# SCH_MSX_nano_mouse_v0_4_2024-05-15.net
KiCad netlist of a schematic drawn in EasyEDA
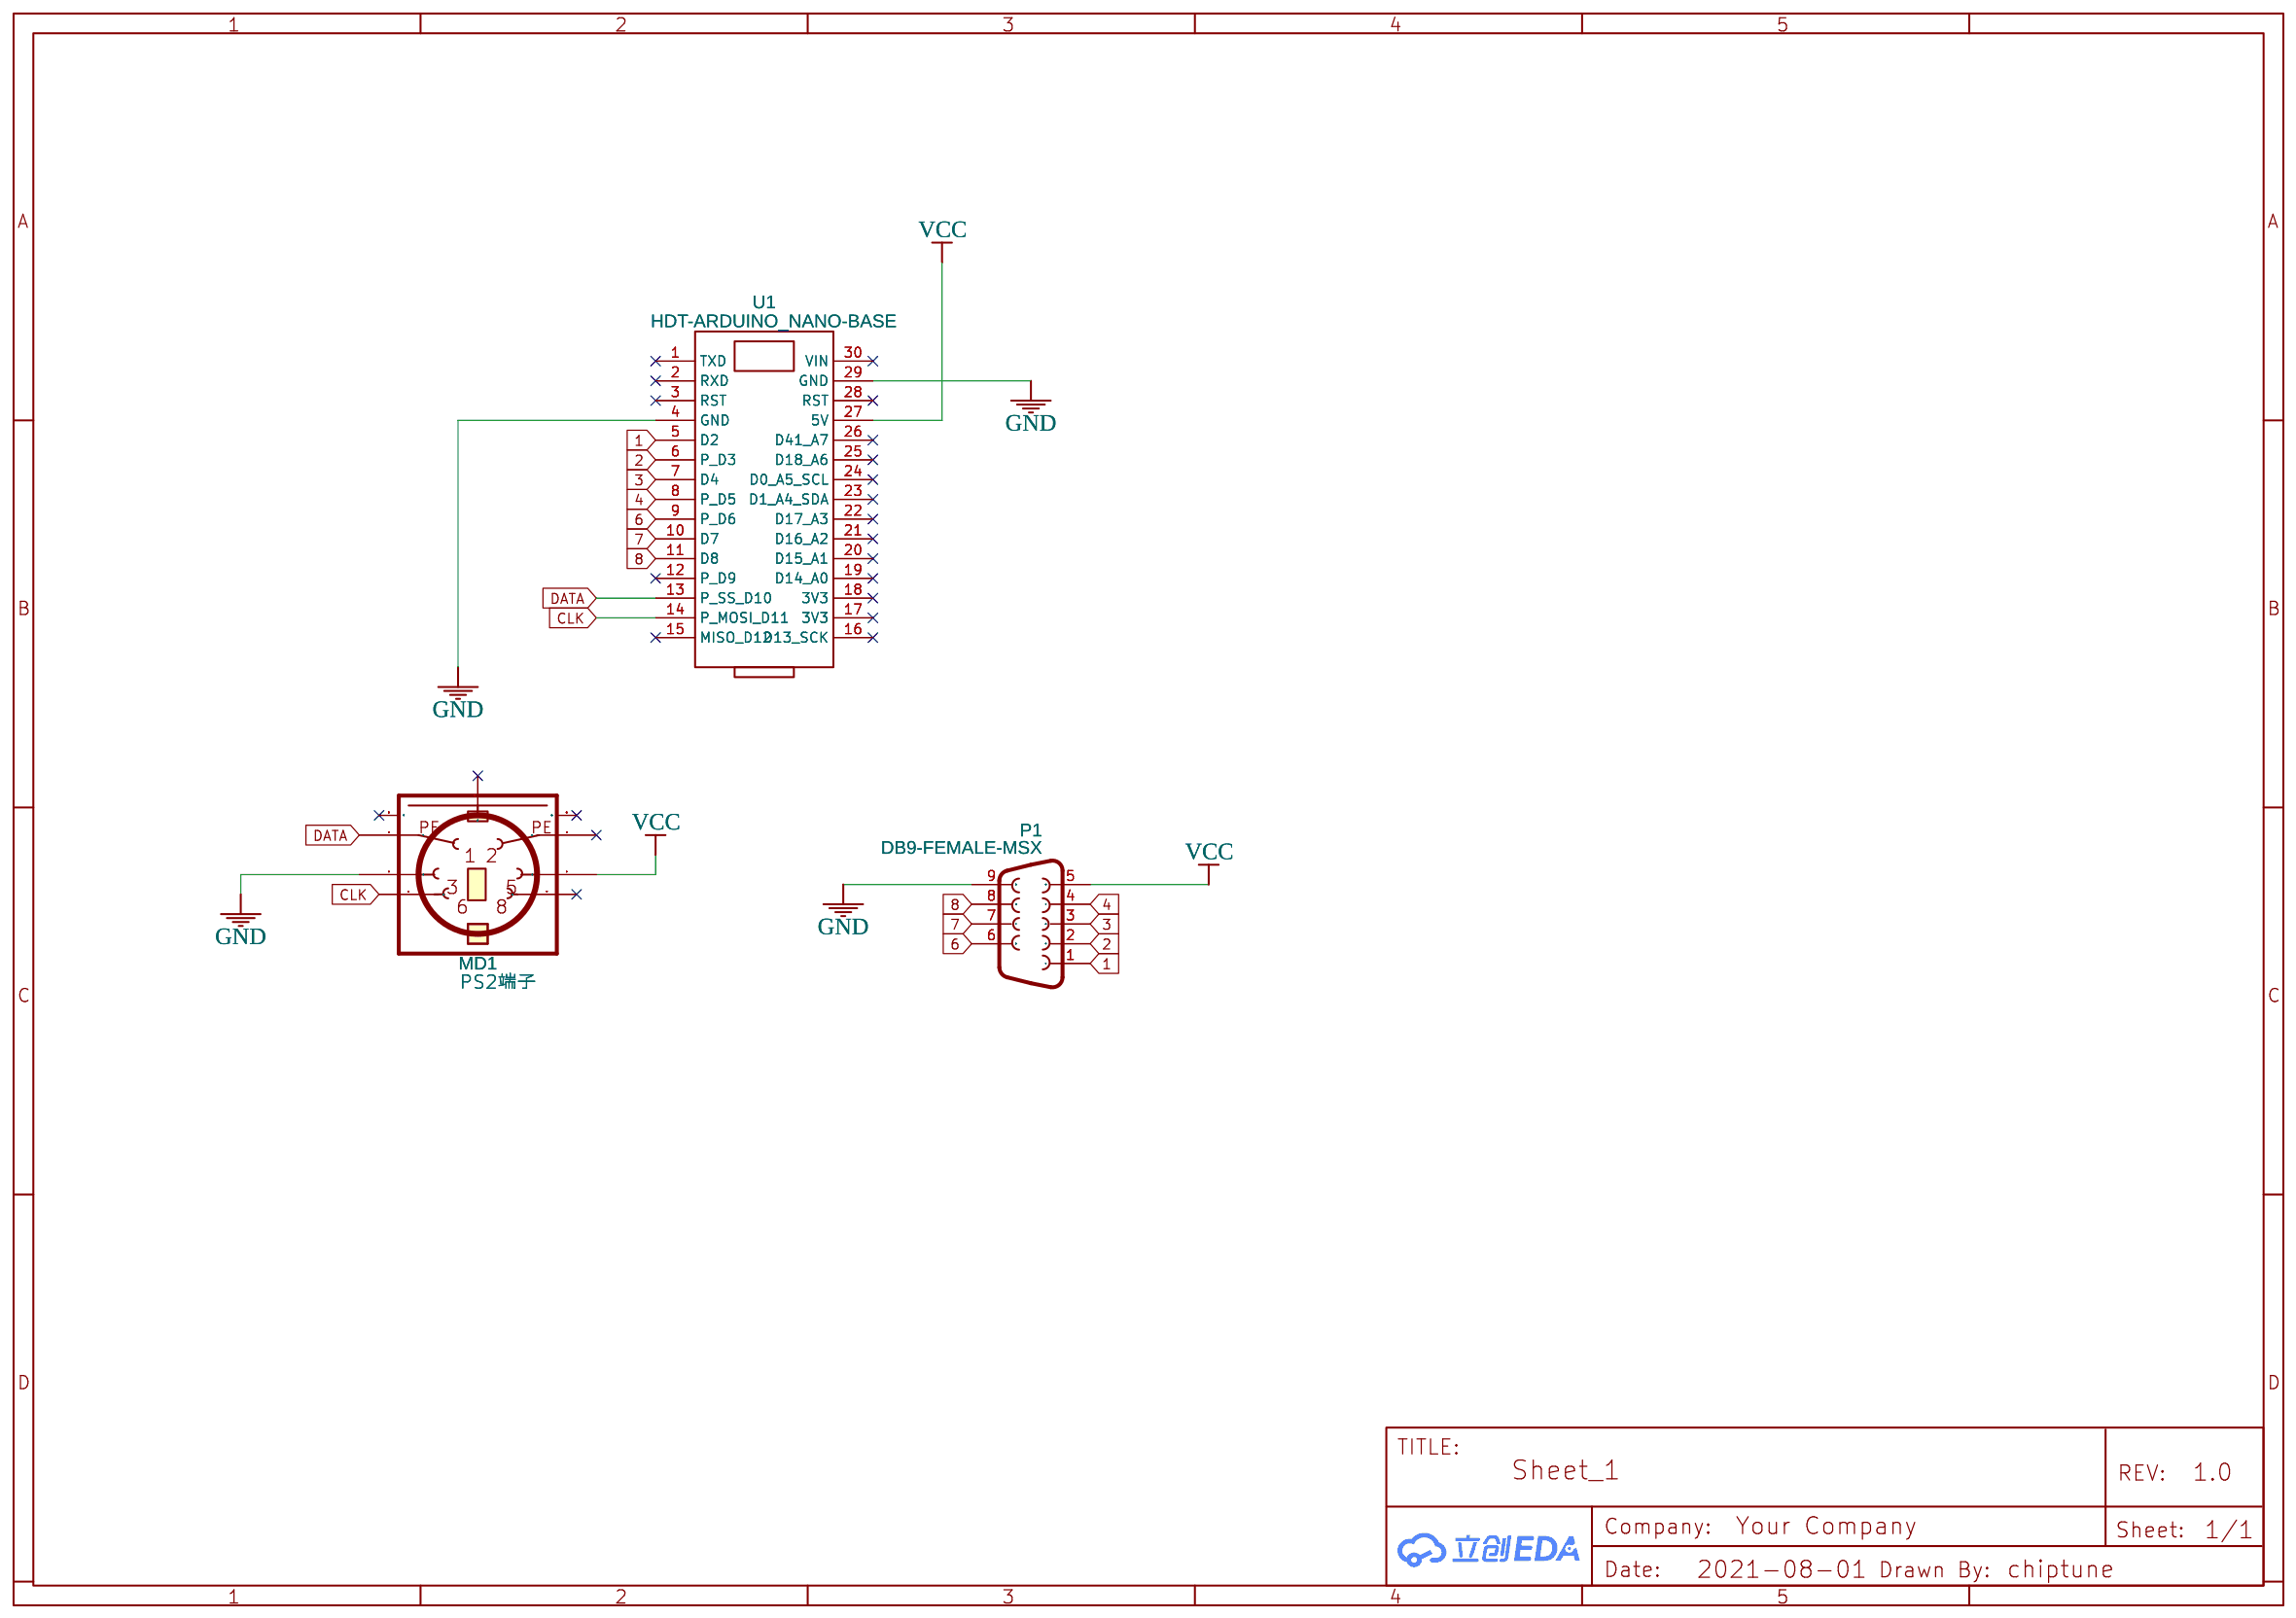
[diagram p0: schematic sheet]

(export (version "E")
  (design (tool "Eeschema 10.0.6"))
  (components
    (comp (ref "MD1")
      (value "PS2端子")
      (fields (field (name "Manufacturer Part") "HYC03-MDC603-128B") (field (name "Manufacturer") "华宇创"))
      (libsource (lib "") (part "PS2端子"))
    )
    (comp (ref "P1") (value "DB9-FEMALE-MSX") (libsource (lib "") (part "DB9-FEMALE-MSX")))
    (comp (ref "U1")
      (value "HDT-ARDUINO_NANO-BASE")
      (fields (field (name "Manufacturer Part") "arduino-nano"))
      (libsource (lib "") (part "HDT-ARDUINO_NANO-BASE"))
    )
  )
  (nets
    (net (code "1") (name "1") (class "Default")
      (node (ref "P1") (pin "1") (pinfunction "1_1") (pintype "unspecified"))
      (node (ref "U1") (pin "5") (pinfunction "D2_5") (pintype "unspecified"))
    )
    (net (code "2") (name "2") (class "Default")
      (node (ref "P1") (pin "2") (pinfunction "2_2") (pintype "unspecified"))
      (node (ref "U1") (pin "6") (pinfunction "P_D3_6") (pintype "unspecified"))
    )
    (net (code "3") (name "3") (class "Default")
      (node (ref "P1") (pin "3") (pinfunction "3_3") (pintype "unspecified"))
      (node (ref "U1") (pin "7") (pinfunction "D4_7") (pintype "unspecified"))
    )
    (net (code "4") (name "4") (class "Default")
      (node (ref "P1") (pin "4") (pinfunction "4_4") (pintype "unspecified"))
      (node (ref "U1") (pin "8") (pinfunction "P_D5_8") (pintype "unspecified"))
    )
    (net (code "5") (name "6") (class "Default")
      (node (ref "P1") (pin "6") (pinfunction "6_6") (pintype "unspecified"))
      (node (ref "U1") (pin "9") (pinfunction "P_D6_9") (pintype "unspecified"))
    )
    (net (code "6") (name "7") (class "Default")
      (node (ref "P1") (pin "7") (pinfunction "7_7") (pintype "unspecified"))
      (node (ref "U1") (pin "10") (pinfunction "D7_10") (pintype "unspecified"))
    )
    (net (code "7") (name "8") (class "Default")
      (node (ref "P1") (pin "8") (pinfunction "8_8") (pintype "unspecified"))
      (node (ref "U1") (pin "11") (pinfunction "D8_11") (pintype "unspecified"))
    )
    (net (code "8") (name "CLK") (class "Default")
      (node (ref "MD1") (pin "6") (pinfunction "6_6") (pintype "unspecified"))
      (node (ref "U1") (pin "14") (pinfunction "P_MOSI_D11_14") (pintype "unspecified"))
    )
    (net (code "9") (name "DATA") (class "Default")
      (node (ref "MD1") (pin "1") (pinfunction "1_1") (pintype "unspecified"))
      (node (ref "U1") (pin "13") (pinfunction "P_SS_D10_13") (pintype "unspecified"))
    )
    (net (code "10") (name "GND") (class "Default")
      (node (ref "MD1") (pin "3") (pinfunction "3_3") (pintype "unspecified"))
      (node (ref "P1") (pin "9") (pinfunction "9_9") (pintype "unspecified"))
      (node (ref "U1") (pin "29") (pinfunction "GND_29") (pintype "unspecified"))
      (node (ref "U1") (pin "4") (pinfunction "GND_4") (pintype "unspecified"))
    )
    (net (code "11") (name "VCC") (class "Default")
      (node (ref "MD1") (pin "5") (pinfunction "5_5") (pintype "unspecified"))
      (node (ref "P1") (pin "5") (pinfunction "5_5") (pintype "unspecified"))
      (node (ref "U1") (pin "27") (pinfunction "5V_27") (pintype "unspecified"))
    )
    (net (code "12") (name "unconnected-(MD1-PE1-PadSH1)") (class "Default")
      (node (ref "MD1") (pin "SH1") (pinfunction "PE1_SH1") (pintype "passive+no_connect"))
    )
    (net (code "13") (name "unconnected-(MD1-PE2-PadSH2)") (class "Default")
      (node (ref "MD1") (pin "SH2") (pinfunction "PE2_SH2") (pintype "passive+no_connect"))
    )
    (net (code "14") (name "unconnected-(MD1-PE3-PadSH3)") (class "Default")
      (node (ref "MD1") (pin "SH3") (pinfunction "PE3_SH3") (pintype "passive+no_connect"))
    )
    (net (code "15") (name "unconnected-(MD1-Pad2)") (class "Default")
      (node (ref "MD1") (pin "2") (pinfunction "2_2") (pintype "unspecified+no_connect"))
    )
    (net (code "16") (name "unconnected-(MD1-Pad8)") (class "Default")
      (node (ref "MD1") (pin "8") (pinfunction "8_8") (pintype "unspecified+no_connect"))
    )
    (net (code "17") (name "unconnected-(U1-3V3-Pad17)") (class "Default")
      (node (ref "U1") (pin "17") (pinfunction "3V3_17") (pintype "unspecified+no_connect"))
    )
    (net (code "18") (name "unconnected-(U1-3V3-Pad18)") (class "Default")
      (node (ref "U1") (pin "18") (pinfunction "3V3_18") (pintype "unspecified+no_connect"))
    )
    (net (code "19") (name "unconnected-(U1-D0_A5_SCL-Pad24)") (class "Default")
      (node (ref "U1") (pin "24") (pinfunction "D0_A5_SCL_24") (pintype "unspecified+no_connect"))
    )
    (net (code "20") (name "unconnected-(U1-D1_A4_SDA-Pad23)") (class "Default")
      (node (ref "U1") (pin "23") (pinfunction "D1_A4_SDA_23") (pintype "unspecified+no_connect"))
    )
    (net (code "21") (name "unconnected-(U1-D13_SCK-Pad16)") (class "Default")
      (node (ref "U1") (pin "16") (pinfunction "D13_SCK_16") (pintype "unspecified+no_connect"))
    )
    (net (code "22") (name "unconnected-(U1-D14_A0-Pad19)") (class "Default")
      (node (ref "U1") (pin "19") (pinfunction "D14_A0_19") (pintype "unspecified+no_connect"))
    )
    (net (code "23") (name "unconnected-(U1-D15_A1-Pad20)") (class "Default")
      (node (ref "U1") (pin "20") (pinfunction "D15_A1_20") (pintype "unspecified+no_connect"))
    )
    (net (code "24") (name "unconnected-(U1-D16_A2-Pad21)") (class "Default")
      (node (ref "U1") (pin "21") (pinfunction "D16_A2_21") (pintype "unspecified+no_connect"))
    )
    (net (code "25") (name "unconnected-(U1-D17_A3-Pad22)") (class "Default")
      (node (ref "U1") (pin "22") (pinfunction "D17_A3_22") (pintype "unspecified+no_connect"))
    )
    (net (code "26") (name "unconnected-(U1-D18_A6-Pad25)") (class "Default")
      (node (ref "U1") (pin "25") (pinfunction "D18_A6_25") (pintype "unspecified+no_connect"))
    )
    (net (code "27") (name "unconnected-(U1-D41_A7-Pad26)") (class "Default")
      (node (ref "U1") (pin "26") (pinfunction "D41_A7_26") (pintype "unspecified+no_connect"))
    )
    (net (code "28") (name "unconnected-(U1-MISO_D12-Pad15)") (class "Default")
      (node (ref "U1") (pin "15") (pinfunction "MISO_D12_15") (pintype "unspecified+no_connect"))
    )
    (net (code "29") (name "unconnected-(U1-P_D9-Pad12)") (class "Default")
      (node (ref "U1") (pin "12") (pinfunction "P_D9_12") (pintype "unspecified+no_connect"))
    )
    (net (code "30") (name "unconnected-(U1-RST-Pad3)") (class "Default")
      (node (ref "U1") (pin "3") (pinfunction "RST_3") (pintype "unspecified+no_connect"))
    )
    (net (code "31") (name "unconnected-(U1-RST-Pad28)") (class "Default")
      (node (ref "U1") (pin "28") (pinfunction "RST_28") (pintype "unspecified+no_connect"))
    )
    (net (code "32") (name "unconnected-(U1-RXD-Pad2)") (class "Default")
      (node (ref "U1") (pin "2") (pinfunction "RXD_2") (pintype "unspecified+no_connect"))
    )
    (net (code "33") (name "unconnected-(U1-TXD-Pad1)") (class "Default")
      (node (ref "U1") (pin "1") (pinfunction "TXD_1") (pintype "unspecified+no_connect"))
    )
    (net (code "34") (name "unconnected-(U1-VIN-Pad30)") (class "Default")
      (node (ref "U1") (pin "30") (pinfunction "VIN_30") (pintype "unspecified+no_connect"))
    )
  )
)
